# db9smt.net
KiCad netlist of a schematic drawn in EAGLE
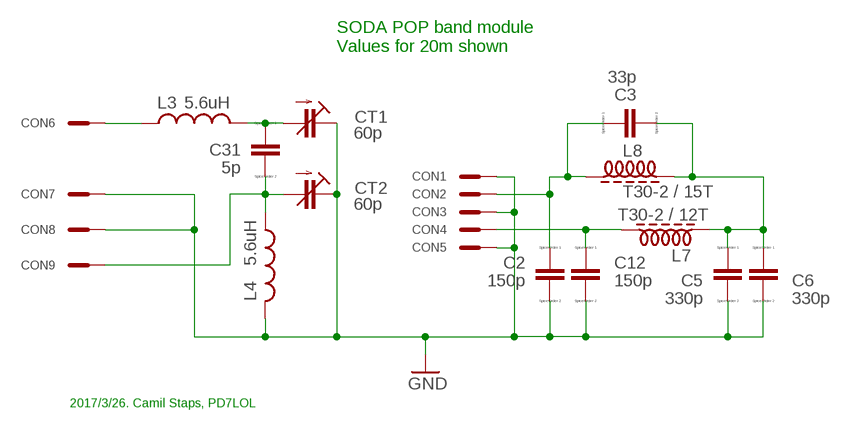
[diagram p0: schematic, sheet 1]

(export (version "E")
  (design (tool "Eeschema 10.0.6"))
  (components
    (comp (ref "C2")
      (value "150p")
      (footprint "eagle-import:C0603")
      (libsource (lib "eagle-import") (part "CC0603"))
    )
    (comp (ref "C3")
      (value "33p")
      (footprint "eagle-import:C0603")
      (libsource (lib "eagle-import") (part "CC0603"))
    )
    (comp (ref "C5")
      (value "330p")
      (footprint "eagle-import:C0603")
      (libsource (lib "eagle-import") (part "CC0603"))
    )
    (comp (ref "C6")
      (value "330p")
      (footprint "eagle-import:C0603")
      (libsource (lib "eagle-import") (part "CC0603"))
    )
    (comp (ref "C12")
      (value "150p")
      (footprint "eagle-import:C0603")
      (libsource (lib "eagle-import") (part "CC0603"))
    )
    (comp (ref "C31")
      (value "5p")
      (footprint "eagle-import:C0603")
      (libsource (lib "eagle-import") (part "CC0603"))
    )
    (comp (ref "CON1")
      (value "PADONPRINT")
      (footprint "eagle-import:PAD")
      (libsource (lib "eagle-import") (part "PADONPRINT"))
    )
    (comp (ref "CON2")
      (value "PADONPRINT")
      (footprint "eagle-import:PAD")
      (libsource (lib "eagle-import") (part "PADONPRINT"))
    )
    (comp (ref "CON3")
      (value "PADONPRINT")
      (footprint "eagle-import:PAD")
      (libsource (lib "eagle-import") (part "PADONPRINT"))
    )
    (comp (ref "CON4")
      (value "PADONPRINT")
      (footprint "eagle-import:PAD")
      (libsource (lib "eagle-import") (part "PADONPRINT"))
    )
    (comp (ref "CON5")
      (value "PADONPRINT")
      (footprint "eagle-import:PAD")
      (libsource (lib "eagle-import") (part "PADONPRINT"))
    )
    (comp (ref "CON6")
      (value "PADONPRINT")
      (footprint "eagle-import:PAD")
      (libsource (lib "eagle-import") (part "PADONPRINT"))
    )
    (comp (ref "CON7")
      (value "PADONPRINT")
      (footprint "eagle-import:PAD")
      (libsource (lib "eagle-import") (part "PADONPRINT"))
    )
    (comp (ref "CON8")
      (value "PADONPRINT")
      (footprint "eagle-import:PAD")
      (libsource (lib "eagle-import") (part "PADONPRINT"))
    )
    (comp (ref "CON9")
      (value "PADONPRINT")
      (footprint "eagle-import:PAD")
      (libsource (lib "eagle-import") (part "PADONPRINT"))
    )
    (comp (ref "CT1")
      (value "60p")
      (footprint "eagle-import:CTRIMTZ03")
      (libsource (lib "eagle-import") (part "C-TRIMMTZ03"))
    )
    (comp (ref "CT2")
      (value "60p")
      (footprint "eagle-import:CTRIMTZ03")
      (libsource (lib "eagle-import") (part "C-TRIMMTZ03"))
    )
    (comp (ref "L3")
      (value "5.6uH")
      (footprint "eagle-import:L2012C")
      (libsource (lib "eagle-import") (part "L-USL2012C"))
    )
    (comp (ref "L4")
      (value "5.6uH")
      (footprint "eagle-import:L2012C")
      (libsource (lib "eagle-import") (part "L-USL2012C"))
    )
    (comp (ref "L7")
      (value "T30-2 / 12T")
      (footprint "eagle-import:T30-2-28AWG-15T")
      (libsource (lib "eagle-import") (part "INDUCTORT30-2-28AWG-15T"))
    )
    (comp (ref "L8")
      (value "T30-2 / 15T")
      (footprint "eagle-import:T30-2-28AWG-15T")
      (libsource (lib "eagle-import") (part "INDUCTORT30-2-28AWG-15T"))
    )
  )
  (nets
    (net (code "1") (name "GND") (class "Default")
      (node (ref "C12") (pin "2") (pinfunction "2_2") (pintype "passive"))
      (node (ref "C2") (pin "2") (pinfunction "2_2") (pintype "passive"))
      (node (ref "C5") (pin "2") (pinfunction "2_2") (pintype "passive"))
      (node (ref "C6") (pin "2") (pinfunction "2_2") (pintype "passive"))
      (node (ref "CON1") (pin "P$1") (pinfunction "P$1_P$1") (pintype "bidirectional"))
      (node (ref "CON3") (pin "P$1") (pinfunction "P$1_P$1") (pintype "bidirectional"))
      (node (ref "CON5") (pin "P$1") (pinfunction "P$1_P$1") (pintype "bidirectional"))
      (node (ref "CON7") (pin "P$1") (pinfunction "P$1_P$1") (pintype "bidirectional"))
      (node (ref "CON8") (pin "P$1") (pinfunction "P$1_P$1") (pintype "bidirectional"))
      (node (ref "CT1") (pin "1") (pinfunction "E_1") (pintype "passive"))
      (node (ref "CT2") (pin "1") (pinfunction "E_1") (pintype "passive"))
      (node (ref "L4") (pin "2") (pinfunction "2_2") (pintype "passive"))
    )
    (net (code "2") (name "Net-(CON6-PadP$1)") (class "Default")
      (node (ref "CON6") (pin "P$1") (pinfunction "P$1_P$1") (pintype "bidirectional"))
      (node (ref "L3") (pin "1") (pinfunction "1_1") (pintype "passive"))
    )
    (net (code "3") (name "Net-(CT1-A)") (class "Default")
      (node (ref "C31") (pin "1") (pinfunction "1_1") (pintype "passive"))
      (node (ref "CT1") (pin "2") (pinfunction "A_2") (pintype "passive"))
      (node (ref "L3") (pin "2") (pinfunction "2_2") (pintype "passive"))
    )
    (net (code "4") (name "Net-(CT2-A)") (class "Default")
      (node (ref "C31") (pin "2") (pinfunction "2_2") (pintype "passive"))
      (node (ref "CON9") (pin "P$1") (pinfunction "P$1_P$1") (pintype "bidirectional"))
      (node (ref "CT2") (pin "2") (pinfunction "A_2") (pintype "passive"))
      (node (ref "L4") (pin "1") (pinfunction "1_1") (pintype "passive"))
    )
    (net (code "5") (name "Net-(L7-1)") (class "Default")
      (node (ref "C3") (pin "2") (pinfunction "2_2") (pintype "passive"))
      (node (ref "C5") (pin "1") (pinfunction "1_1") (pintype "passive"))
      (node (ref "C6") (pin "1") (pinfunction "1_1") (pintype "passive"))
      (node (ref "L7") (pin "P$1") (pinfunction "1_P$1") (pintype "passive"))
      (node (ref "L8") (pin "P$2") (pinfunction "2_P$2") (pintype "passive"))
    )
    (net (code "6") (name "Net-(L7-2)") (class "Default")
      (node (ref "C12") (pin "1") (pinfunction "1_1") (pintype "passive"))
      (node (ref "CON4") (pin "P$1") (pinfunction "P$1_P$1") (pintype "bidirectional"))
      (node (ref "L7") (pin "P$2") (pinfunction "2_P$2") (pintype "passive"))
    )
    (net (code "7") (name "Net-(L8-1)") (class "Default")
      (node (ref "C2") (pin "1") (pinfunction "1_1") (pintype "passive"))
      (node (ref "C3") (pin "1") (pinfunction "1_1") (pintype "passive"))
      (node (ref "CON2") (pin "P$1") (pinfunction "P$1_P$1") (pintype "bidirectional"))
      (node (ref "L8") (pin "P$1") (pinfunction "1_P$1") (pintype "passive"))
    )
  )
)
